# Microcontroller.net
KiCad netlist of a schematic drawn in Altium Designer
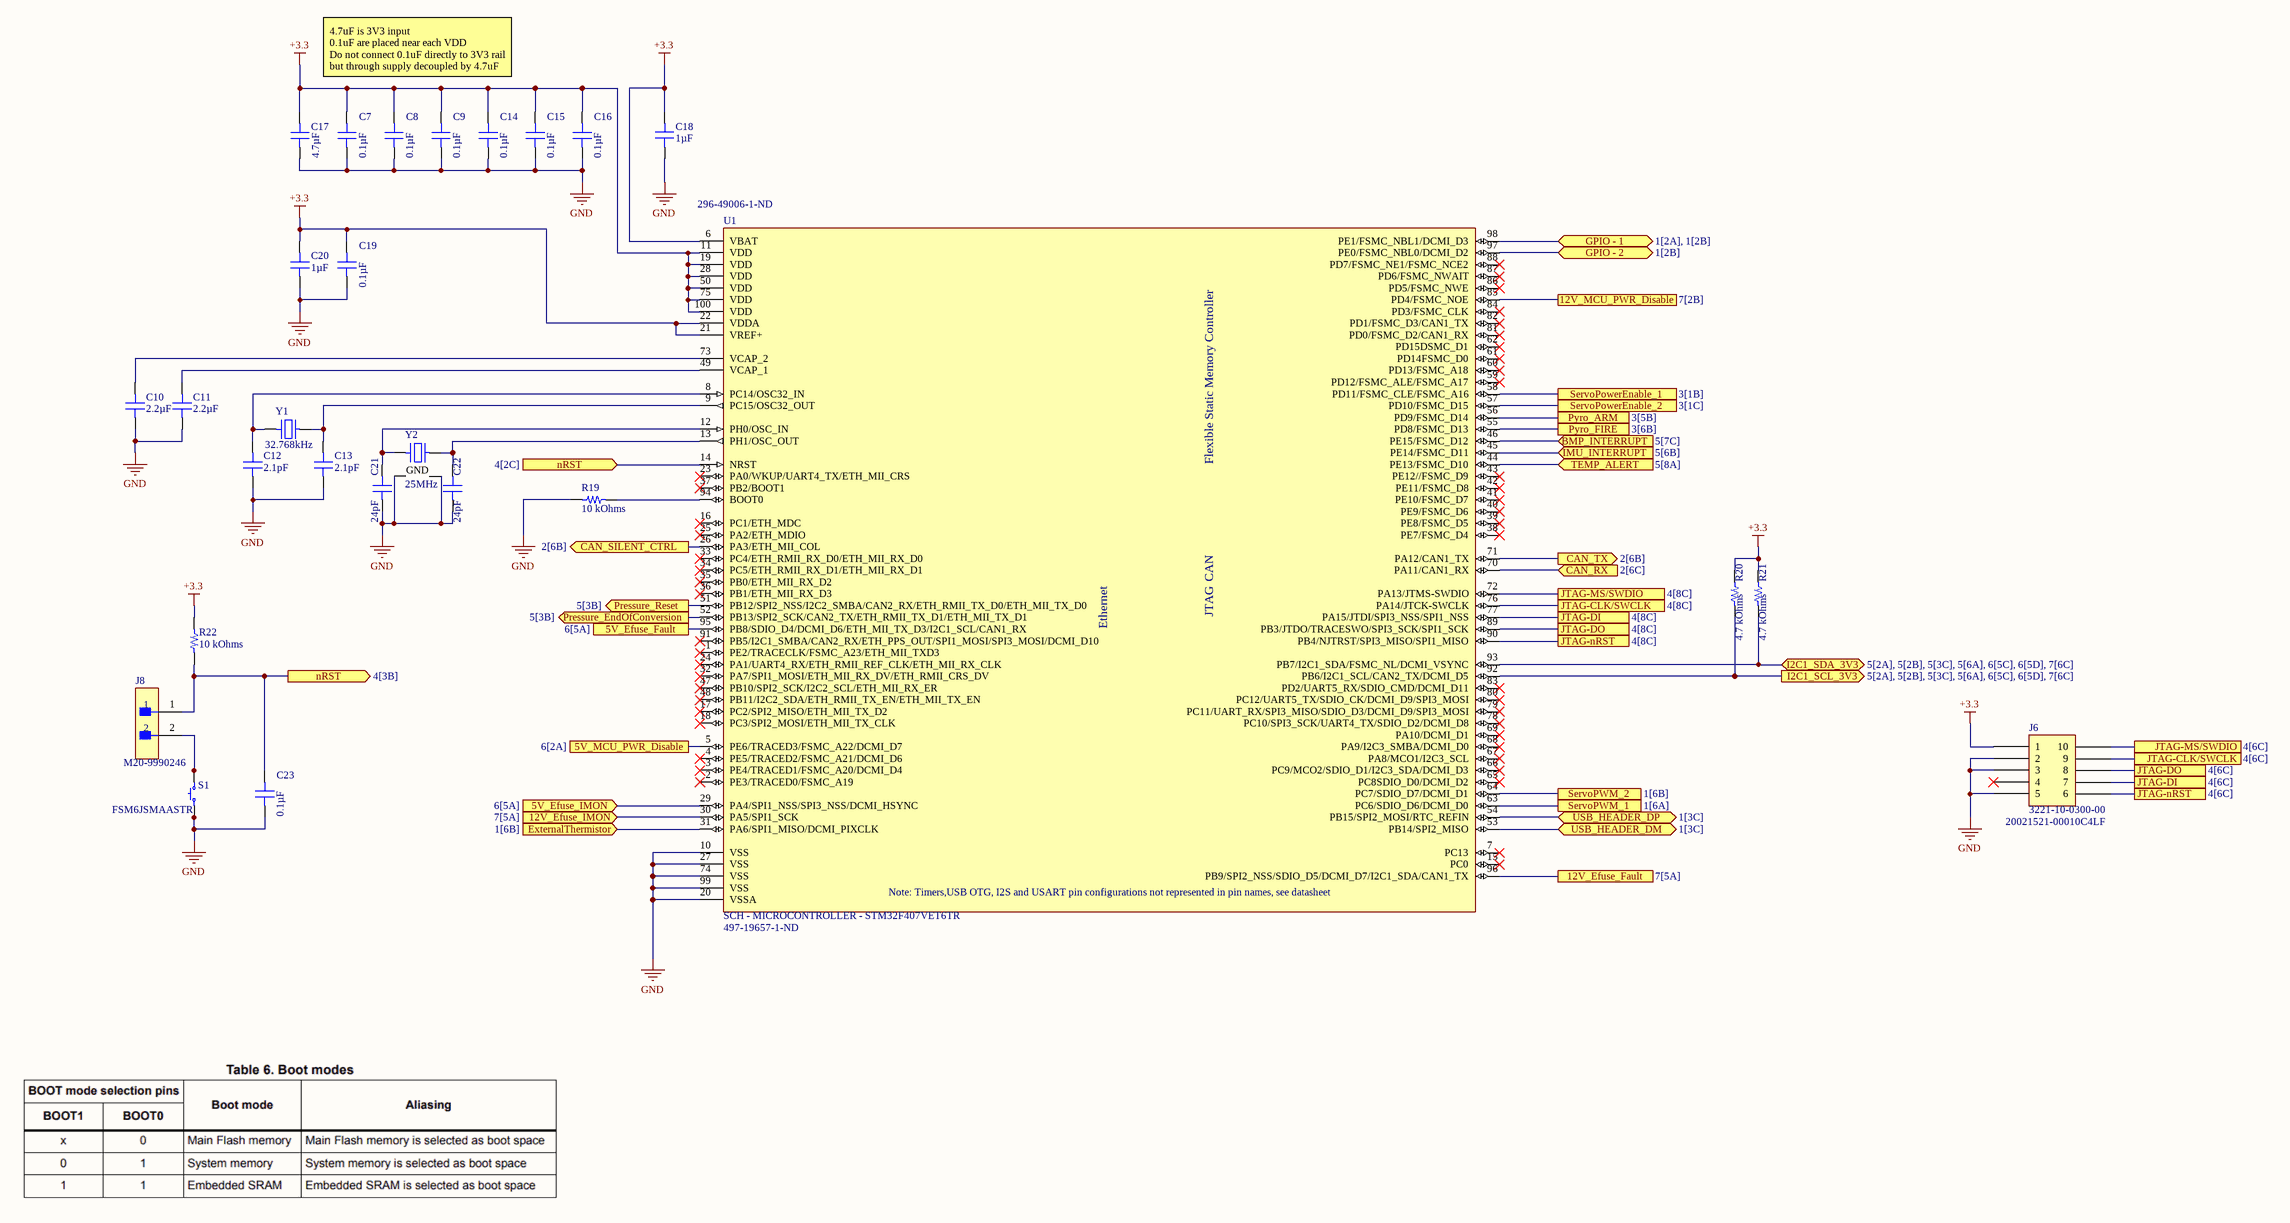
[diagram p0: Microcontroller.SchDoc]

(export (version "E")
  (design (tool "Eeschema 10.0.6"))
  (components
    (comp (ref "C7")
      (value "0.1µF")
      (footprint "CAP 0603_1608")
      (description "CAP CER 0.1UF 25V X7R 0603")
      (fields
        (field (name "PART NUMBER") "CL10B104KA8WPNC")
        (field (name "MANUFACTURER") "Samsung Electro-Mechanics")
      )
      (libsource (lib "Celestial Altium Library - altium_library") (part "Capacitor"))
    )
    (comp (ref "C8")
      (value "0.1µF")
      (footprint "CAP 0603_1608")
      (description "CAP CER 0.1UF 25V X7R 0603")
      (fields
        (field (name "PART NUMBER") "CL10B104KA8WPNC")
        (field (name "MANUFACTURER") "Samsung Electro-Mechanics")
      )
      (libsource (lib "Celestial Altium Library - altium_library") (part "Capacitor"))
    )
    (comp (ref "C9")
      (value "0.1µF")
      (footprint "CAP 0603_1608")
      (description "CAP CER 0.1UF 25V X7R 0603")
      (fields
        (field (name "PART NUMBER") "CL10B104KA8WPNC")
        (field (name "MANUFACTURER") "Samsung Electro-Mechanics")
      )
      (libsource (lib "Celestial Altium Library - altium_library") (part "Capacitor"))
    )
    (comp (ref "C10")
      (value "2.2µF")
      (footprint "CAP 0603_1608")
      (description "CAP CER 2.2UF 16V X5R 0603")
      (fields (field (name "PART NUMBER") "EMK107BJ225KA-T") (field (name "MANUFACTURER") "Taiyo Yuden"))
      (libsource (lib "Celestial Altium Library - altium_library") (part "Capacitor"))
    )
    (comp (ref "C11")
      (value "2.2µF")
      (footprint "CAP 0603_1608")
      (description "CAP CER 2.2UF 16V X5R 0603")
      (fields (field (name "PART NUMBER") "EMK107BJ225KA-T") (field (name "MANUFACTURER") "Taiyo Yuden"))
      (libsource (lib "Celestial Altium Library - altium_library") (part "Capacitor"))
    )
    (comp (ref "C12")
      (value "2.1pF")
      (footprint "CAP 0603_1608")
      (description "CAP CER RF 2.1PF 50V +/-0.1 PF C")
      (fields (field (name "PART NUMBER") "CBR06C219B5GAC") (field (name "MANUFACTURER") "KEMET"))
      (libsource (lib "Celestial Altium Library - altium_library") (part "Capacitor"))
    )
    (comp (ref "C13")
      (value "2.1pF")
      (footprint "CAP 0603_1608")
      (description "CAP CER RF 2.1PF 50V +/-0.1 PF C")
      (fields (field (name "PART NUMBER") "CBR06C219B5GAC") (field (name "MANUFACTURER") "KEMET"))
      (libsource (lib "Celestial Altium Library - altium_library") (part "Capacitor"))
    )
    (comp (ref "C14")
      (value "0.1µF")
      (footprint "CAP 0603_1608")
      (description "CAP CER 0.1UF 25V X7R 0603")
      (fields
        (field (name "PART NUMBER") "CL10B104KA8WPNC")
        (field (name "MANUFACTURER") "Samsung Electro-Mechanics")
      )
      (libsource (lib "Celestial Altium Library - altium_library") (part "Capacitor"))
    )
    (comp (ref "C15")
      (value "0.1µF")
      (footprint "CAP 0603_1608")
      (description "CAP CER 0.1UF 25V X7R 0603")
      (fields
        (field (name "PART NUMBER") "CL10B104KA8WPNC")
        (field (name "MANUFACTURER") "Samsung Electro-Mechanics")
      )
      (libsource (lib "Celestial Altium Library - altium_library") (part "Capacitor"))
    )
    (comp (ref "C16")
      (value "0.1µF")
      (footprint "CAP 0603_1608")
      (description "CAP CER 0.1UF 25V X7R 0603")
      (fields
        (field (name "PART NUMBER") "CL10B104KA8WPNC")
        (field (name "MANUFACTURER") "Samsung Electro-Mechanics")
      )
      (libsource (lib "Celestial Altium Library - altium_library") (part "Capacitor"))
    )
    (comp (ref "C17")
      (value "4.7µF")
      (footprint "CAP 0603_1608")
      (description "CAP CER 4.7UF 16V X5R 0603")
      (fields
        (field (name "PART NUMBER") "C1608X5R1C475K080AC")
        (field (name "MANUFACTURER") "TDK Corporation")
      )
      (libsource (lib "Celestial Altium Library - altium_library") (part "Capacitor"))
    )
    (comp (ref "C18")
      (value "1µF")
      (footprint "CAP 0603_1608")
      (description "CAP CER 1UF 16V X7R 0603")
      (fields
        (field (name "PART NUMBER") "GCM188R71C105KA64J")
        (field (name "MANUFACTURER") "Murata Electronics")
      )
      (libsource (lib "Celestial Altium Library - altium_library") (part "Capacitor"))
    )
    (comp (ref "C19")
      (value "0.1µF")
      (footprint "CAP 0603_1608")
      (description "CAP CER 0.1UF 25V X7R 0603")
      (fields
        (field (name "PART NUMBER") "CL10B104KA8WPNC")
        (field (name "MANUFACTURER") "Samsung Electro-Mechanics")
      )
      (libsource (lib "Celestial Altium Library - altium_library") (part "Capacitor"))
    )
    (comp (ref "C20")
      (value "1µF")
      (footprint "CAP 0603_1608")
      (description "CAP CER 1UF 16V X7R 0603")
      (fields
        (field (name "PART NUMBER") "GCM188R71C105KA64J")
        (field (name "MANUFACTURER") "Murata Electronics")
      )
      (libsource (lib "Celestial Altium Library - altium_library") (part "Capacitor"))
    )
    (comp (ref "C21")
      (value "24pF")
      (footprint "CAP 0603_1608")
      (description "CAP CER 24PF 50V C0G/NP0 0603")
      (fields
        (field (name "PART NUMBER") "CL10C240JB8NNNC")
        (field (name "MANUFACTURER") "Samsung Electro-Mechanics")
      )
      (libsource (lib "Celestial Altium Library - altium_library") (part "Capacitor"))
    )
    (comp (ref "C22")
      (value "24pF")
      (footprint "CAP 0603_1608")
      (description "CAP CER 24PF 50V C0G/NP0 0603")
      (fields
        (field (name "PART NUMBER") "CL10C240JB8NNNC")
        (field (name "MANUFACTURER") "Samsung Electro-Mechanics")
      )
      (libsource (lib "Celestial Altium Library - altium_library") (part "Capacitor"))
    )
    (comp (ref "C23")
      (value "0.1µF")
      (footprint "CAP 0603_1608")
      (description "CAP CER 0.1UF 25V X7R 0603")
      (fields
        (field (name "PART NUMBER") "CL10B104KA8WPNC")
        (field (name "MANUFACTURER") "Samsung Electro-Mechanics")
      )
      (libsource (lib "Celestial Altium Library - altium_library") (part "Capacitor"))
    )
    (comp (ref "J6")
      (value "3221-10-0300-00")
      (footprint "CNC TECH 3221-10-0300-00")
      (description "CONN HEADER SMD 10POS 1.27MM")
      (fields (field (name "MANUFACTURER") "CNC Tech"))
      (libsource (lib "Celestial Altium Library - altium_library") (part "2x5 Pin"))
    )
    (comp (ref "J8")
      (value "M20-9990246")
      (footprint "FP-M20-9990246-MFG")
      (description "CONN HEADER VERT 2POS 2.54MM")
      (fields
        (field (name "OCTOPART") "https://octopart.com/m20-9990246-harwin-2590635")
        (field (name "MANUFACTURER") "Harwin")
      )
      (libsource (lib "Altium Content Vault") (part "3bc925449376181038e59eaffc5286c"))
    )
    (comp (ref "R19")
      (value "10 kOhms")
      (footprint "RES 0603_1608")
      (description "RES 10K OHM 5% 1/10W 0603")
      (fields
        (field (name "PART NUMBER") "RMCF0603JT10K0")
        (field (name "MANUFACTURER") "Stackpole Electronics Inc")
      )
      (libsource (lib "Celestial Altium Library - altium_library") (part "Resistor"))
    )
    (comp (ref "R20")
      (value "4.7 kOhms")
      (footprint "RES 0603_1608")
      (description "RES 4.7K OHM 1% 1/10W 0603")
      (fields
        (field (name "PART NUMBER") "RMCF0603FT4K70")
        (field (name "MANUFACTURER") "Stackpole Electronics Inc")
      )
      (libsource (lib "Celestial Altium Library - altium_library") (part "Resistor"))
    )
    (comp (ref "R21")
      (value "4.7 kOhms")
      (footprint "RES 0603_1608")
      (description "RES 4.7K OHM 1% 1/10W 0603")
      (fields
        (field (name "PART NUMBER") "RMCF0603FT4K70")
        (field (name "MANUFACTURER") "Stackpole Electronics Inc")
      )
      (libsource (lib "Celestial Altium Library - altium_library") (part "Resistor"))
    )
    (comp (ref "R22")
      (value "10 kOhms")
      (footprint "RES 0603_1608")
      (description "RES 10K OHM 5% 1/10W 0603")
      (fields
        (field (name "PART NUMBER") "RMCF0603JT10K0")
        (field (name "MANUFACTURER") "Stackpole Electronics Inc")
      )
      (libsource (lib "Celestial Altium Library - altium_library") (part "Resistor"))
    )
    (comp (ref "S1")
      (value "FSM6JSMAASTR")
      (footprint "TE FSM6JSMA")
      (description "SWITCH TACTILE SPST-NO 0.05A 24V")
      (fields (field (name "MANUFACTURER") "TE Connectivity ALCOSWITCH Switches"))
      (libsource (lib "Celestial Altium Library - altium_library") (part "SPST-NO 4 PIN"))
    )
    (comp (ref "U1")
      (value "SCH - MICROCONTROLLER - STM32F407VET6TR")
      (footprint "PCB - LEADLESS - QFP - ST LQFP-100 14X14MM")
      (fields (field (name "SUPPLIER PART NUMBER 1") "497-19657-1-ND"))
      (libsource (lib "HAB_ICs") (part "SCH - MICROCONTROLLER - STM32F407VET6TR"))
    )
    (comp (ref "Y1")
      (value "32.768kHz")
      (footprint "ABRACON ABS07")
      (description "IOT 32.786KHZ XTAL")
      (fields
        (field (name "PART NUMBER") "ABS07-166-32.768KHZ-T")
        (field (name "MANUFACTURER") "Abracon LLC")
      )
      (libsource (lib "Celestial Altium Library - altium_library") (part "Abracon Crystal ABS07"))
    )
    (comp (ref "Y2")
      (value "25MHz")
      (footprint "EPSON TSX-3225")
      (description "CRYSTAL 25.0000MHZ 18PF SMD")
      (fields (field (name "PART NUMBER") "TSX-3225 25.0000MF20P-C0") (field (name "MANUFACTURER") "EPSON"))
      (libsource (lib "Celestial Altium Library - altium_library") (part "Epson Crystal TSX-3225"))
    )
  )
  (nets
    (net (code "1") (name "+3.3") (class "Default")
      (node (ref "C14") (pin "2") (pinfunction "2_2") (pintype "passive"))
      (node (ref "C15") (pin "2") (pinfunction "2_2") (pintype "passive"))
      (node (ref "C16") (pin "2") (pinfunction "2_2") (pintype "passive"))
      (node (ref "C17") (pin "2") (pinfunction "2_2") (pintype "passive"))
      (node (ref "C18") (pin "2") (pinfunction "2_2") (pintype "passive"))
      (node (ref "C19") (pin "2") (pinfunction "2_2") (pintype "passive"))
      (node (ref "C20") (pin "2") (pinfunction "2_2") (pintype "passive"))
      (node (ref "C7") (pin "2") (pinfunction "2_2") (pintype "passive"))
      (node (ref "C8") (pin "2") (pinfunction "2_2") (pintype "passive"))
      (node (ref "C9") (pin "2") (pinfunction "2_2") (pintype "passive"))
      (node (ref "J6") (pin "1") (pinfunction "1_1") (pintype "passive"))
      (node (ref "R20") (pin "2") (pinfunction "2_2") (pintype "passive"))
      (node (ref "R21") (pin "2") (pinfunction "2_2") (pintype "passive"))
      (node (ref "R22") (pin "1") (pinfunction "1_1") (pintype "passive"))
      (node (ref "U1") (pin "100") (pinfunction "VDD_100") (pintype "power_in"))
      (node (ref "U1") (pin "11") (pinfunction "VDD_11") (pintype "power_in"))
      (node (ref "U1") (pin "19") (pinfunction "VDD_19") (pintype "power_in"))
      (node (ref "U1") (pin "21") (pinfunction "VREF+_21") (pintype "power_in"))
      (node (ref "U1") (pin "22") (pinfunction "VDDA_22") (pintype "power_in"))
      (node (ref "U1") (pin "28") (pinfunction "VDD_28") (pintype "power_in"))
      (node (ref "U1") (pin "50") (pinfunction "VDD_50") (pintype "power_in"))
      (node (ref "U1") (pin "6") (pinfunction "VBAT_6") (pintype "power_in"))
      (node (ref "U1") (pin "75") (pinfunction "VDD_75") (pintype "power_in"))
    )
    (net (code "2") (name "/5V_Efuse_Fault") (class "Default")
      (node (ref "U1") (pin "95") (pinfunction "PB8/SDIO_D4/DCMI_D6/ETH_MII_TX_D3/I2C1_SCL/CAN1_RX_95") (pintype "bidirectional"))
    )
    (net (code "3") (name "/5V_Efuse_IMON") (class "Default")
      (node (ref "U1") (pin "29") (pinfunction "PA4/SPI1_NSS/SPI3_NSS/DCMI_HSYNC_29") (pintype "bidirectional"))
    )
    (net (code "4") (name "/5V_MCU_PWR_Disable") (class "Default")
      (node (ref "U1") (pin "5") (pinfunction "PE6/TRACED3/FSMC_A22/DCMI_D7_5") (pintype "bidirectional"))
    )
    (net (code "5") (name "/12V_Efuse_Fault") (class "Default")
      (node (ref "U1") (pin "96") (pinfunction "PB9/SPI2_NSS/SDIO_D5/DCMI_D7/I2C1_SDA/CAN1_TX_96") (pintype "bidirectional"))
    )
    (net (code "6") (name "/12V_Efuse_IMON") (class "Default")
      (node (ref "U1") (pin "30") (pinfunction "PA5/SPI1_SCK_30") (pintype "bidirectional"))
    )
    (net (code "7") (name "/12V_MCU_PWR_Disable") (class "Default")
      (node (ref "U1") (pin "85") (pinfunction "PD4/FSMC_NOE_85") (pintype "bidirectional"))
    )
    (net (code "8") (name "/BMP_INTERRUPT") (class "Default")
      (node (ref "U1") (pin "46") (pinfunction "PE15/FSMC_D12_46") (pintype "bidirectional"))
    )
    (net (code "9") (name "/CAN_RX") (class "Default")
      (node (ref "U1") (pin "70") (pinfunction "PA11/CAN1_RX_70") (pintype "bidirectional"))
    )
    (net (code "10") (name "/CAN_SILENT_CTRL") (class "Default")
      (node (ref "U1") (pin "26") (pinfunction "PA3/ETH_MII_COL_26") (pintype "bidirectional"))
    )
    (net (code "11") (name "/CAN_TX") (class "Default")
      (node (ref "U1") (pin "71") (pinfunction "PA12/CAN1_TX_71") (pintype "bidirectional"))
    )
    (net (code "12") (name "/ExternalThermistor") (class "Default")
      (node (ref "U1") (pin "31") (pinfunction "PA6/SPI1_MISO/DCMI_PIXCLK_31") (pintype "bidirectional"))
    )
    (net (code "13") (name "/GPIO - 1") (class "Default")
      (node (ref "U1") (pin "98") (pinfunction "PE1/FSMC_NBL1/DCMI_D3_98") (pintype "bidirectional"))
    )
    (net (code "14") (name "/GPIO - 2") (class "Default")
      (node (ref "U1") (pin "97") (pinfunction "PE0/FSMC_NBL0/DCMI_D2_97") (pintype "bidirectional"))
    )
    (net (code "15") (name "/I2C1_SCL_3V3") (class "Default")
      (node (ref "R20") (pin "1") (pinfunction "1_1") (pintype "passive"))
      (node (ref "U1") (pin "92") (pinfunction "PB6/I2C1_SCL/CAN2_TX/DCMI_D5_92") (pintype "bidirectional"))
    )
    (net (code "16") (name "/I2C1_SDA_3V3") (class "Default")
      (node (ref "R21") (pin "1") (pinfunction "1_1") (pintype "passive"))
      (node (ref "U1") (pin "93") (pinfunction "PB7/I2C1_SDA/FSMC_NL/DCMI_VSYNC_93") (pintype "bidirectional"))
    )
    (net (code "17") (name "/IMU_INTERRUPT") (class "Default")
      (node (ref "U1") (pin "45") (pinfunction "PE14/FSMC_D11_45") (pintype "bidirectional"))
    )
    (net (code "18") (name "/JTAG-CLK{slash}SWCLK") (class "Default")
      (node (ref "J6") (pin "9") (pinfunction "9_9") (pintype "passive"))
      (node (ref "U1") (pin "76") (pinfunction "PA14/JTCK-SWCLK_76") (pintype "bidirectional"))
    )
    (net (code "19") (name "/JTAG-DI") (class "Default")
      (node (ref "J6") (pin "7") (pinfunction "7_7") (pintype "passive"))
      (node (ref "U1") (pin "77") (pinfunction "PA15/JTDI/SPI3_NSS/SPI1_NSS_77") (pintype "bidirectional"))
    )
    (net (code "20") (name "/JTAG-DO") (class "Default")
      (node (ref "J6") (pin "8") (pinfunction "8_8") (pintype "passive"))
      (node (ref "U1") (pin "89") (pinfunction "PB3/JTDO/TRACESWO/SPI3_SCK/SPI1_SCK_89") (pintype "bidirectional"))
    )
    (net (code "21") (name "/JTAG-MS{slash}SWDIO") (class "Default")
      (node (ref "J6") (pin "10") (pinfunction "10_10") (pintype "passive"))
      (node (ref "U1") (pin "72") (pinfunction "PA13/JTMS-SWDIO_72") (pintype "bidirectional"))
    )
    (net (code "22") (name "/JTAG-nRST") (class "Default")
      (node (ref "J6") (pin "6") (pinfunction "6_6") (pintype "passive"))
      (node (ref "U1") (pin "90") (pinfunction "PB4/NJTRST/SPI3_MISO/SPI1_MISO_90") (pintype "bidirectional"))
    )
    (net (code "23") (name "/Pressure_EndOfConversion") (class "Default")
      (node (ref "U1") (pin "52") (pinfunction "PB13/SPI2_SCK/CAN2_TX/ETH_RMII_TX_D1/ETH_MII_TX_D1_52") (pintype "bidirectional"))
    )
    (net (code "24") (name "/Pressure_Reset") (class "Default")
      (node (ref "U1") (pin "51") (pinfunction "PB12/SPI2_NSS/I2C2_SMBA/CAN2_RX/ETH_RMII_TX_D0/ETH_MII_TX_D0_51") (pintype "bidirectional"))
    )
    (net (code "25") (name "/Pyro_ARM") (class "Default")
      (node (ref "U1") (pin "56") (pinfunction "PD9/FSMC_D14_56") (pintype "bidirectional"))
    )
    (net (code "26") (name "/Pyro_FIRE") (class "Default")
      (node (ref "U1") (pin "55") (pinfunction "PD8/FSMC_D13_55") (pintype "bidirectional"))
    )
    (net (code "27") (name "/ServoPWM_1") (class "Default")
      (node (ref "U1") (pin "63") (pinfunction "PC6/SDIO_D6/DCMI_D0_63") (pintype "bidirectional"))
    )
    (net (code "28") (name "/ServoPWM_2") (class "Default")
      (node (ref "U1") (pin "64") (pinfunction "PC7/SDIO_D7/DCMI_D1_64") (pintype "bidirectional"))
    )
    (net (code "29") (name "/ServoPowerEnable_1") (class "Default")
      (node (ref "U1") (pin "58") (pinfunction "PD11/FSMC_CLE/FSMC_A16_58") (pintype "bidirectional"))
    )
    (net (code "30") (name "/ServoPowerEnable_2") (class "Default")
      (node (ref "U1") (pin "57") (pinfunction "PD10/FSMC_D15_57") (pintype "bidirectional"))
    )
    (net (code "31") (name "/TEMP_ALERT") (class "Default")
      (node (ref "U1") (pin "44") (pinfunction "PE13/FSMC_D10_44") (pintype "bidirectional"))
    )
    (net (code "32") (name "/USB_HEADER_DM") (class "Default")
      (node (ref "U1") (pin "53") (pinfunction "PB14/SPI2_MISO_53") (pintype "bidirectional"))
    )
    (net (code "33") (name "/USB_HEADER_DP") (class "Default")
      (node (ref "U1") (pin "54") (pinfunction "PB15/SPI2_MOSI/RTC_REFIN_54") (pintype "bidirectional"))
    )
    (net (code "34") (name "/nRST") (class "Default")
      (node (ref "C23") (pin "2") (pinfunction "2_2") (pintype "passive"))
      (node (ref "J8") (pin "1") (pinfunction "1_1") (pintype "passive"))
      (node (ref "R22") (pin "2") (pinfunction "2_2") (pintype "passive"))
      (node (ref "U1") (pin "14") (pinfunction "NRST_14") (pintype "input"))
    )
    (net (code "35") (name "GND") (class "Default")
      (node (ref "C10") (pin "1") (pinfunction "1_1") (pintype "passive"))
      (node (ref "C11") (pin "1") (pinfunction "1_1") (pintype "passive"))
      (node (ref "C12") (pin "1") (pinfunction "1_1") (pintype "passive"))
      (node (ref "C13") (pin "1") (pinfunction "1_1") (pintype "passive"))
      (node (ref "C14") (pin "1") (pinfunction "1_1") (pintype "passive"))
      (node (ref "C15") (pin "1") (pinfunction "1_1") (pintype "passive"))
      (node (ref "C16") (pin "1") (pinfunction "1_1") (pintype "passive"))
      (node (ref "C17") (pin "1") (pinfunction "1_1") (pintype "passive"))
      (node (ref "C18") (pin "1") (pinfunction "1_1") (pintype "passive"))
      (node (ref "C19") (pin "1") (pinfunction "1_1") (pintype "passive"))
      (node (ref "C20") (pin "1") (pinfunction "1_1") (pintype "passive"))
      (node (ref "C21") (pin "1") (pinfunction "1_1") (pintype "passive"))
      (node (ref "C22") (pin "1") (pinfunction "1_1") (pintype "passive"))
      (node (ref "C23") (pin "1") (pinfunction "1_1") (pintype "passive"))
      (node (ref "C7") (pin "1") (pinfunction "1_1") (pintype "passive"))
      (node (ref "C8") (pin "1") (pinfunction "1_1") (pintype "passive"))
      (node (ref "C9") (pin "1") (pinfunction "1_1") (pintype "passive"))
      (node (ref "J6") (pin "2") (pinfunction "2_2") (pintype "passive"))
      (node (ref "J6") (pin "3") (pinfunction "3_3") (pintype "passive"))
      (node (ref "J6") (pin "5") (pinfunction "5_5") (pintype "passive"))
      (node (ref "R19") (pin "2") (pinfunction "2_2") (pintype "passive"))
      (node (ref "S1") (pin "1") (pinfunction "1_1") (pintype "passive"))
      (node (ref "S1") (pin "2") (pinfunction "2_2") (pintype "passive"))
      (node (ref "U1") (pin "10") (pinfunction "VSS_10") (pintype "power_in"))
      (node (ref "U1") (pin "20") (pinfunction "VSSA_20") (pintype "power_in"))
      (node (ref "U1") (pin "27") (pinfunction "VSS_27") (pintype "power_in"))
      (node (ref "U1") (pin "74") (pinfunction "VSS_74") (pintype "power_in"))
      (node (ref "U1") (pin "99") (pinfunction "VSS_99") (pintype "power_in"))
      (node (ref "Y2") (pin "2") (pinfunction "GND_2") (pintype "passive"))
      (node (ref "Y2") (pin "4") (pinfunction "GND_4") (pintype "passive"))
    )
    (net (code "36") (name "Net-(J8-Pad2)") (class "Default")
      (node (ref "J8") (pin "2") (pinfunction "2_2") (pintype "passive"))
      (node (ref "S1") (pin "3") (pinfunction "3_3") (pintype "passive"))
      (node (ref "S1") (pin "4") (pinfunction "4_4") (pintype "passive"))
    )
    (net (code "37") (name "Net-(U1-BOOT0)") (class "Default")
      (node (ref "R19") (pin "1") (pinfunction "1_1") (pintype "passive"))
      (node (ref "U1") (pin "94") (pinfunction "BOOT0_94") (pintype "bidirectional"))
    )
    (net (code "38") (name "Net-(U1-PC14{slash}OSC32_IN)") (class "Default")
      (node (ref "C12") (pin "2") (pinfunction "2_2") (pintype "passive"))
      (node (ref "U1") (pin "8") (pinfunction "PC14/OSC32_IN_8") (pintype "input"))
      (node (ref "Y1") (pin "1") (pinfunction "1_1") (pintype "passive"))
    )
    (net (code "39") (name "Net-(U1-PC15{slash}OSC32_OUT)") (class "Default")
      (node (ref "C13") (pin "2") (pinfunction "2_2") (pintype "passive"))
      (node (ref "U1") (pin "9") (pinfunction "PC15/OSC32_OUT_9") (pintype "output"))
      (node (ref "Y1") (pin "2") (pinfunction "2_2") (pintype "passive"))
    )
    (net (code "40") (name "Net-(U1-PH0{slash}OSC_IN)") (class "Default")
      (node (ref "C21") (pin "2") (pinfunction "2_2") (pintype "passive"))
      (node (ref "U1") (pin "12") (pinfunction "PH0/OSC_IN_12") (pintype "input"))
      (node (ref "Y2") (pin "1") (pinfunction "1_1") (pintype "passive"))
    )
    (net (code "41") (name "Net-(U1-PH1{slash}OSC_OUT)") (class "Default")
      (node (ref "C22") (pin "2") (pinfunction "2_2") (pintype "passive"))
      (node (ref "U1") (pin "13") (pinfunction "PH1/OSC_OUT_13") (pintype "output"))
      (node (ref "Y2") (pin "3") (pinfunction "3_3") (pintype "passive"))
    )
    (net (code "42") (name "Net-(U1-VCAP_1)") (class "Default")
      (node (ref "C11") (pin "2") (pinfunction "2_2") (pintype "passive"))
      (node (ref "U1") (pin "49") (pinfunction "VCAP_1_49") (pintype "power_in"))
    )
    (net (code "43") (name "Net-(U1-VCAP_2)") (class "Default")
      (node (ref "C10") (pin "2") (pinfunction "2_2") (pintype "passive"))
      (node (ref "U1") (pin "73") (pinfunction "VCAP_2_73") (pintype "power_in"))
    )
    (net (code "44") (name "unconnected-(J6-Pad4)") (class "Default")
      (node (ref "J6") (pin "4") (pinfunction "4_4") (pintype "passive+no_connect"))
    )
    (net (code "45") (name "unconnected-(U1-PA0{slash}WKUP{slash}UART4_TX{slash}ETH_MII_CRS-Pad23)") (class "Default")
      (node (ref "U1") (pin "23") (pinfunction "PA0/WKUP/UART4_TX/ETH_MII_CRS_23") (pintype "bidirectional+no_connect"))
    )
    (net (code "46") (name "unconnected-(U1-PA1{slash}UART4_RX{slash}ETH_RMII_REF_CLK{slash}ETH_MII_RX_CLK-Pad24)") (class "Default")
      (node (ref "U1") (pin "24") (pinfunction "PA1/UART4_RX/ETH_RMII_REF_CLK/ETH_MII_RX_CLK_24") (pintype "bidirectional+no_connect"))
    )
    (net (code "47") (name "unconnected-(U1-PA2{slash}ETH_MDIO-Pad25)") (class "Default")
      (node (ref "U1") (pin "25") (pinfunction "PA2/ETH_MDIO_25") (pintype "bidirectional+no_connect"))
    )
    (net (code "48") (name "unconnected-(U1-PA7{slash}SPI1_MOSI{slash}ETH_MII_RX_DV{slash}ETH_RMII_CRS_DV-Pad32)") (class "Default")
      (node (ref "U1") (pin "32") (pinfunction "PA7/SPI1_MOSI/ETH_MII_RX_DV/ETH_RMII_CRS_DV_32") (pintype "bidirectional+no_connect"))
    )
    (net (code "49") (name "unconnected-(U1-PA8{slash}MCO1{slash}I2C3_SCL-Pad67)") (class "Default")
      (node (ref "U1") (pin "67") (pinfunction "PA8/MCO1/I2C3_SCL_67") (pintype "bidirectional+no_connect"))
    )
    (net (code "50") (name "unconnected-(U1-PA9{slash}I2C3_SMBA{slash}DCMI_D0-Pad68)") (class "Default")
      (node (ref "U1") (pin "68") (pinfunction "PA9/I2C3_SMBA/DCMI_D0_68") (pintype "bidirectional+no_connect"))
    )
    (net (code "51") (name "unconnected-(U1-PA10{slash}DCMI_D1-Pad69)") (class "Default")
      (node (ref "U1") (pin "69") (pinfunction "PA10/DCMI_D1_69") (pintype "bidirectional+no_connect"))
    )
    (net (code "52") (name "unconnected-(U1-PB0{slash}ETH_MII_RX_D2-Pad35)") (class "Default")
      (node (ref "U1") (pin "35") (pinfunction "PB0/ETH_MII_RX_D2_35") (pintype "bidirectional+no_connect"))
    )
    (net (code "53") (name "unconnected-(U1-PB1{slash}ETH_MII_RX_D3-Pad36)") (class "Default")
      (node (ref "U1") (pin "36") (pinfunction "PB1/ETH_MII_RX_D3_36") (pintype "bidirectional+no_connect"))
    )
    (net (code "54") (name "unconnected-(U1-PB2{slash}BOOT1-Pad37)") (class "Default")
      (node (ref "U1") (pin "37") (pinfunction "PB2/BOOT1_37") (pintype "bidirectional+no_connect"))
    )
    (net (code "55") (name "unconnected-(U1-PB5{slash}I2C1_SMBA{slash}CAN2_RX{slash}ETH_PPS_OUT{slash}SPI1_MOSI{slash}SPI3_MOSI{slash}DCMI_D10-Pad91)") (class "Default")
      (node (ref "U1") (pin "91") (pinfunction "PB5/I2C1_SMBA/CAN2_RX/ETH_PPS_OUT/SPI1_MOSI/SPI3_MOSI/DCMI_D10_91") (pintype "bidirectional+no_connect"))
    )
    (net (code "56") (name "unconnected-(U1-PB10{slash}SPI2_SCK{slash}I2C2_SCL{slash}ETH_MII_RX_ER-Pad47)") (class "Default")
      (node (ref "U1") (pin "47") (pinfunction "PB10/SPI2_SCK/I2C2_SCL/ETH_MII_RX_ER_47") (pintype "bidirectional+no_connect"))
    )
    (net (code "57") (name "unconnected-(U1-PB11{slash}I2C2_SDA{slash}ETH_RMII_TX_EN{slash}ETH_MII_TX_EN-Pad48)") (class "Default")
      (node (ref "U1") (pin "48") (pinfunction "PB11/I2C2_SDA/ETH_RMII_TX_EN/ETH_MII_TX_EN_48") (pintype "bidirectional+no_connect"))
    )
    (net (code "58") (name "unconnected-(U1-PC0-Pad15)") (class "Default")
      (node (ref "U1") (pin "15") (pinfunction "PC0_15") (pintype "bidirectional+no_connect"))
    )
    (net (code "59") (name "unconnected-(U1-PC1{slash}ETH_MDC-Pad16)") (class "Default")
      (node (ref "U1") (pin "16") (pinfunction "PC1/ETH_MDC_16") (pintype "bidirectional+no_connect"))
    )
    (net (code "60") (name "unconnected-(U1-PC2{slash}SPI2_MISO{slash}ETH_MII_TX_D2-Pad17)") (class "Default")
      (node (ref "U1") (pin "17") (pinfunction "PC2/SPI2_MISO/ETH_MII_TX_D2_17") (pintype "bidirectional+no_connect"))
    )
    (net (code "61") (name "unconnected-(U1-PC3{slash}SPI2_MOSI{slash}ETH_MII_TX_CLK-Pad18)") (class "Default")
      (node (ref "U1") (pin "18") (pinfunction "PC3/SPI2_MOSI/ETH_MII_TX_CLK_18") (pintype "bidirectional+no_connect"))
    )
    (net (code "62") (name "unconnected-(U1-PC4{slash}ETH_RMII_RX_D0{slash}ETH_MII_RX_D0-Pad33)") (class "Default")
      (node (ref "U1") (pin "33") (pinfunction "PC4/ETH_RMII_RX_D0/ETH_MII_RX_D0_33") (pintype "bidirectional+no_connect"))
    )
    (net (code "63") (name "unconnected-(U1-PC5{slash}ETH_RMII_RX_D1{slash}ETH_MII_RX_D1-Pad34)") (class "Default")
      (node (ref "U1") (pin "34") (pinfunction "PC5/ETH_RMII_RX_D1/ETH_MII_RX_D1_34") (pintype "bidirectional+no_connect"))
    )
    (net (code "64") (name "unconnected-(U1-PC8SDIO_D0{slash}DCMI_D2-Pad65)") (class "Default")
      (node (ref "U1") (pin "65") (pinfunction "PC8SDIO_D0/DCMI_D2_65") (pintype "bidirectional+no_connect"))
    )
    (net (code "65") (name "unconnected-(U1-PC9{slash}MCO2{slash}SDIO_D1{slash}I2C3_SDA{slash}DCMI_D3-Pad66)") (class "Default")
      (node (ref "U1") (pin "66") (pinfunction "PC9/MCO2/SDIO_D1/I2C3_SDA/DCMI_D3_66") (pintype "bidirectional+no_connect"))
    )
    (net (code "66") (name "unconnected-(U1-PC10{slash}SPI3_SCK{slash}UART4_TX{slash}SDIO_D2{slash}DCMI_D8-Pad78)") (class "Default")
      (node (ref "U1") (pin "78") (pinfunction "PC10/SPI3_SCK/UART4_TX/SDIO_D2/DCMI_D8_78") (pintype "bidirectional+no_connect"))
    )
    (net (code "67") (name "unconnected-(U1-PC11{slash}UART_RX{slash}SPI3_MISO{slash}SDIO_D3{slash}DCMI_D9{slash}SPI3_MOSI-Pad79)") (class "Default")
      (node (ref "U1") (pin "79") (pinfunction "PC11/UART_RX/SPI3_MISO/SDIO_D3/DCMI_D9/SPI3_MOSI_79") (pintype "bidirectional+no_connect"))
    )
    (net (code "68") (name "unconnected-(U1-PC12{slash}UART5_TX{slash}SDIO_CK{slash}DCMI_D9{slash}SPI3_MOSI-Pad80)") (class "Default")
      (node (ref "U1") (pin "80") (pinfunction "PC12/UART5_TX/SDIO_CK/DCMI_D9/SPI3_MOSI_80") (pintype "bidirectional+no_connect"))
    )
    (net (code "69") (name "unconnected-(U1-PC13-Pad7)") (class "Default")
      (node (ref "U1") (pin "7") (pinfunction "PC13_7") (pintype "bidirectional+no_connect"))
    )
    (net (code "70") (name "unconnected-(U1-PD0{slash}FSMC_D2{slash}CAN1_RX-Pad81)") (class "Default")
      (node (ref "U1") (pin "81") (pinfunction "PD0/FSMC_D2/CAN1_RX_81") (pintype "bidirectional+no_connect"))
    )
    (net (code "71") (name "unconnected-(U1-PD1{slash}FSMC_D3{slash}CAN1_TX-Pad82)") (class "Default")
      (node (ref "U1") (pin "82") (pinfunction "PD1/FSMC_D3/CAN1_TX_82") (pintype "bidirectional+no_connect"))
    )
    (net (code "72") (name "unconnected-(U1-PD2{slash}UART5_RX{slash}SDIO_CMD{slash}DCMI_D11-Pad83)") (class "Default")
      (node (ref "U1") (pin "83") (pinfunction "PD2/UART5_RX/SDIO_CMD/DCMI_D11_83") (pintype "bidirectional+no_connect"))
    )
    (net (code "73") (name "unconnected-(U1-PD3{slash}FSMC_CLK-Pad84)") (class "Default")
      (node (ref "U1") (pin "84") (pinfunction "PD3/FSMC_CLK_84") (pintype "bidirectional+no_connect"))
    )
    (net (code "74") (name "unconnected-(U1-PD5{slash}FSMC_NWE-Pad86)") (class "Default")
      (node (ref "U1") (pin "86") (pinfunction "PD5/FSMC_NWE_86") (pintype "bidirectional+no_connect"))
    )
    (net (code "75") (name "unconnected-(U1-PD6{slash}FSMC_NWAIT-Pad87)") (class "Default")
      (node (ref "U1") (pin "87") (pinfunction "PD6/FSMC_NWAIT_87") (pintype "bidirectional+no_connect"))
    )
    (net (code "76") (name "unconnected-(U1-PD7{slash}FSMC_NE1{slash}FSMC_NCE2-Pad88)") (class "Default")
      (node (ref "U1") (pin "88") (pinfunction "PD7/FSMC_NE1/FSMC_NCE2_88") (pintype "bidirectional+no_connect"))
    )
    (net (code "77") (name "unconnected-(U1-PD12{slash}FSMC_ALE{slash}FSMC_A17-Pad59)") (class "Default")
      (node (ref "U1") (pin "59") (pinfunction "PD12/FSMC_ALE/FSMC_A17_59") (pintype "bidirectional+no_connect"))
    )
    (net (code "78") (name "unconnected-(U1-PD13{slash}FSMC_A18-Pad60)") (class "Default")
      (node (ref "U1") (pin "60") (pinfunction "PD13/FSMC_A18_60") (pintype "bidirectional+no_connect"))
    )
    (net (code "79") (name "unconnected-(U1-PD14FSMC_D0-Pad61)") (class "Default")
      (node (ref "U1") (pin "61") (pinfunction "PD14FSMC_D0_61") (pintype "bidirectional+no_connect"))
    )
    (net (code "80") (name "unconnected-(U1-PD15DSMC_D1-Pad62)") (class "Default")
      (node (ref "U1") (pin "62") (pinfunction "PD15DSMC_D1_62") (pintype "bidirectional+no_connect"))
    )
    (net (code "81") (name "unconnected-(U1-PE2{slash}TRACECLK{slash}FSMC_A23{slash}ETH_MII_TXD3-Pad1)") (class "Default")
      (node (ref "U1") (pin "1") (pinfunction "PE2/TRACECLK/FSMC_A23/ETH_MII_TXD3_1") (pintype "bidirectional+no_connect"))
    )
    (net (code "82") (name "unconnected-(U1-PE3{slash}TRACED0{slash}FSMC_A19-Pad2)") (class "Default")
      (node (ref "U1") (pin "2") (pinfunction "PE3/TRACED0/FSMC_A19_2") (pintype "bidirectional+no_connect"))
    )
    (net (code "83") (name "unconnected-(U1-PE4{slash}TRACED1{slash}FSMC_A20{slash}DCMI_D4-Pad3)") (class "Default")
      (node (ref "U1") (pin "3") (pinfunction "PE4/TRACED1/FSMC_A20/DCMI_D4_3") (pintype "bidirectional+no_connect"))
    )
    (net (code "84") (name "unconnected-(U1-PE5{slash}TRACED2{slash}FSMC_A21{slash}DCMI_D6-Pad4)") (class "Default")
      (node (ref "U1") (pin "4") (pinfunction "PE5/TRACED2/FSMC_A21/DCMI_D6_4") (pintype "bidirectional+no_connect"))
    )
    (net (code "85") (name "unconnected-(U1-PE7{slash}FSMC_D4-Pad38)") (class "Default")
      (node (ref "U1") (pin "38") (pinfunction "PE7/FSMC_D4_38") (pintype "bidirectional+no_connect"))
    )
    (net (code "86") (name "unconnected-(U1-PE8{slash}FSMC_D5-Pad39)") (class "Default")
      (node (ref "U1") (pin "39") (pinfunction "PE8/FSMC_D5_39") (pintype "bidirectional+no_connect"))
    )
    (net (code "87") (name "unconnected-(U1-PE9{slash}FSMC_D6-Pad40)") (class "Default")
      (node (ref "U1") (pin "40") (pinfunction "PE9/FSMC_D6_40") (pintype "bidirectional+no_connect"))
    )
    (net (code "88") (name "unconnected-(U1-PE10{slash}FSMC_D7-Pad41)") (class "Default")
      (node (ref "U1") (pin "41") (pinfunction "PE10/FSMC_D7_41") (pintype "bidirectional+no_connect"))
    )
    (net (code "89") (name "unconnected-(U1-PE11{slash}FSMC_D8-Pad42)") (class "Default")
      (node (ref "U1") (pin "42") (pinfunction "PE11/FSMC_D8_42") (pintype "bidirectional+no_connect"))
    )
    (net (code "90") (name "unconnected-(U1-PE12{slash}{slash}FSMC_D9-Pad43)") (class "Default")
      (node (ref "U1") (pin "43") (pinfunction "PE12//FSMC_D9_43") (pintype "bidirectional+no_connect"))
    )
  )
)
